# FPGA_LVDS.net
KiCad netlist of a schematic drawn in Altium Designer
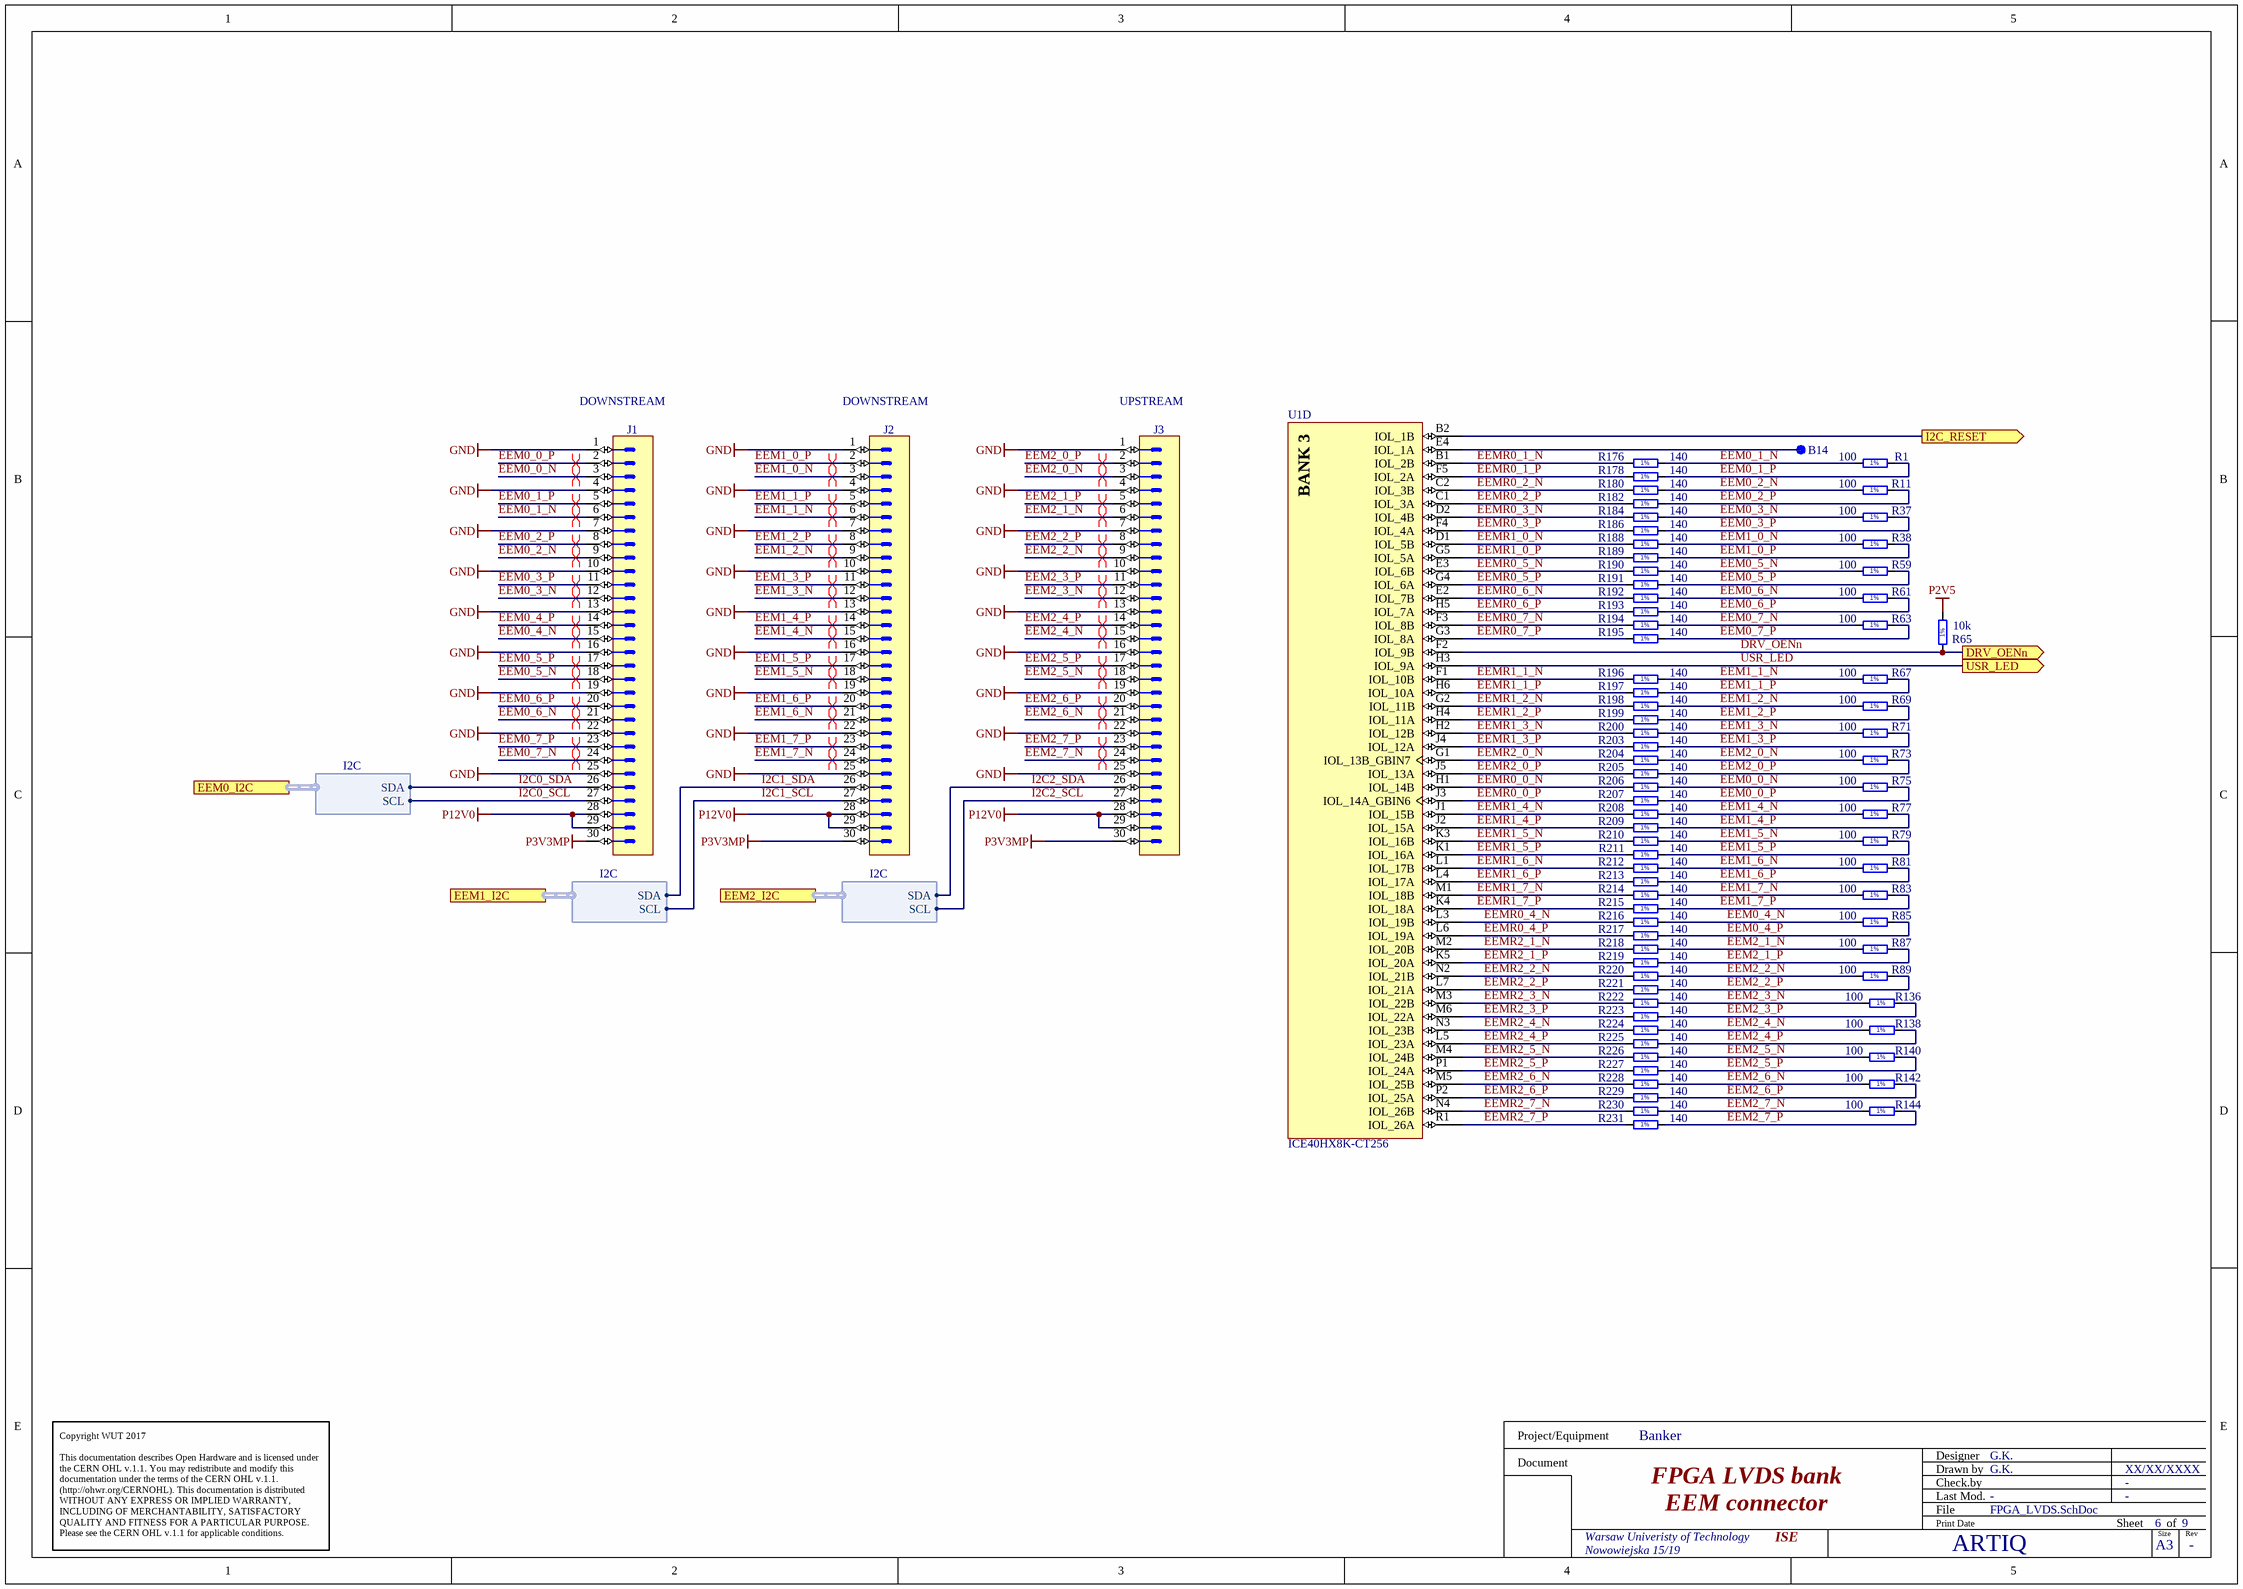
[diagram p0: FPGA_LVDS.SchDoc]

(export (version "E")
  (design (tool "Eeschema 10.0.6"))
  (components
    (comp (ref "B14")
      (value "SMD Pad")
      (footprint "C100")
      (description "Through Hole Pad")
      (fields (field (name "PART NUMBER") "SMD_PAD_D1MM") (field (name "AUTHOR") "CERN DEM JLC"))
      (libsource (lib "Eletro-mechanical") (part "Single SMD Pad (Round)"))
    )
    (comp (ref "J1")
      (value "~")
      (footprint "3M_N2530-6002RB")
      (description "Connector 30 Male")
      (fields
        (field (name "PART NUMBER") "3M_N2530-6002RB")
        (field (name "MANUFACTURER") "3M")
        (field (name "AUTHOR") "CERN DEM JLC")
      )
      (libsource (lib "Connectors") (part "Connector 30 Male"))
    )
    (comp (ref "J2")
      (value "~")
      (footprint "3M_N2530-6002RB")
      (description "Connector 30 Male")
      (fields
        (field (name "PART NUMBER") "3M_N2530-6002RB")
        (field (name "MANUFACTURER") "3M")
        (field (name "AUTHOR") "CERN DEM JLC")
      )
      (libsource (lib "Connectors") (part "Connector 30 Male"))
    )
    (comp (ref "J3")
      (value "~")
      (footprint "3M_N2530-6002RB")
      (description "Connector 30 Male")
      (fields
        (field (name "PART NUMBER") "3M_N2530-6002RB")
        (field (name "MANUFACTURER") "3M")
        (field (name "AUTHOR") "CERN DEM JLC")
      )
      (libsource (lib "Connectors") (part "Connector 30 Male"))
    )
    (comp (ref "R1")
      (value "100")
      (footprint "RESC1005X40N")
      (description "Resistor - 1%")
      (fields
        (field (name "PART NUMBER") "R0402_100R_1%_0.0625W_100PPM")
        (field (name "POWER") "0.0625W")
        (field (name "AUTHOR") "CERN DEM JLC")
      )
      (libsource (lib "Resistors") (part "Resistor - 1%"))
    )
    (comp (ref "R11")
      (value "100")
      (footprint "RESC1005X40N")
      (description "Resistor - 1%")
      (fields
        (field (name "PART NUMBER") "R0402_100R_1%_0.0625W_100PPM")
        (field (name "POWER") "0.0625W")
        (field (name "AUTHOR") "CERN DEM JLC")
      )
      (libsource (lib "Resistors") (part "Resistor - 1%"))
    )
    (comp (ref "R37")
      (value "100")
      (footprint "RESC1005X40N")
      (description "Resistor - 1%")
      (fields
        (field (name "PART NUMBER") "R0402_100R_1%_0.0625W_100PPM")
        (field (name "POWER") "0.0625W")
        (field (name "AUTHOR") "CERN DEM JLC")
      )
      (libsource (lib "Resistors") (part "Resistor - 1%"))
    )
    (comp (ref "R38")
      (value "100")
      (footprint "RESC1005X40N")
      (description "Resistor - 1%")
      (fields
        (field (name "PART NUMBER") "R0402_100R_1%_0.0625W_100PPM")
        (field (name "POWER") "0.0625W")
        (field (name "AUTHOR") "CERN DEM JLC")
      )
      (libsource (lib "Resistors") (part "Resistor - 1%"))
    )
    (comp (ref "R59")
      (value "100")
      (footprint "RESC1005X40N")
      (description "Resistor - 1%")
      (fields
        (field (name "PART NUMBER") "R0402_100R_1%_0.0625W_100PPM")
        (field (name "POWER") "0.0625W")
        (field (name "AUTHOR") "CERN DEM JLC")
      )
      (libsource (lib "Resistors") (part "Resistor - 1%"))
    )
    (comp (ref "R61")
      (value "100")
      (footprint "RESC1005X40N")
      (description "Resistor - 1%")
      (fields
        (field (name "PART NUMBER") "R0402_100R_1%_0.0625W_100PPM")
        (field (name "POWER") "0.0625W")
        (field (name "AUTHOR") "CERN DEM JLC")
      )
      (libsource (lib "Resistors") (part "Resistor - 1%"))
    )
    (comp (ref "R63")
      (value "100")
      (footprint "RESC1005X40N")
      (description "Resistor - 1%")
      (fields
        (field (name "PART NUMBER") "R0402_100R_1%_0.0625W_100PPM")
        (field (name "POWER") "0.0625W")
        (field (name "AUTHOR") "CERN DEM JLC")
      )
      (libsource (lib "Resistors") (part "Resistor - 1%"))
    )
    (comp (ref "R65")
      (value "10k")
      (footprint "RESC1005X40N")
      (description "Resistor - 1%")
      (fields
        (field (name "PART NUMBER") "R0402_10K_1%_0.0625W_100PPM")
        (field (name "POWER") "0.0625W")
        (field (name "AUTHOR") "CERN DEM JLC")
      )
      (libsource (lib "Resistors") (part "Resistor - 1%"))
    )
    (comp (ref "R67")
      (value "100")
      (footprint "RESC1005X40N")
      (description "Resistor - 1%")
      (fields
        (field (name "PART NUMBER") "R0402_100R_1%_0.0625W_100PPM")
        (field (name "POWER") "0.0625W")
        (field (name "AUTHOR") "CERN DEM JLC")
      )
      (libsource (lib "Resistors") (part "Resistor - 1%"))
    )
    (comp (ref "R69")
      (value "100")
      (footprint "RESC1005X40N")
      (description "Resistor - 1%")
      (fields
        (field (name "PART NUMBER") "R0402_100R_1%_0.0625W_100PPM")
        (field (name "POWER") "0.0625W")
        (field (name "AUTHOR") "CERN DEM JLC")
      )
      (libsource (lib "Resistors") (part "Resistor - 1%"))
    )
    (comp (ref "R71")
      (value "100")
      (footprint "RESC1005X40N")
      (description "Resistor - 1%")
      (fields
        (field (name "PART NUMBER") "R0402_100R_1%_0.0625W_100PPM")
        (field (name "POWER") "0.0625W")
        (field (name "AUTHOR") "CERN DEM JLC")
      )
      (libsource (lib "Resistors") (part "Resistor - 1%"))
    )
    (comp (ref "R73")
      (value "100")
      (footprint "RESC1005X40N")
      (description "Resistor - 1%")
      (fields
        (field (name "PART NUMBER") "R0402_100R_1%_0.0625W_100PPM")
        (field (name "POWER") "0.0625W")
        (field (name "AUTHOR") "CERN DEM JLC")
      )
      (libsource (lib "Resistors") (part "Resistor - 1%"))
    )
    (comp (ref "R75")
      (value "100")
      (footprint "RESC1005X40N")
      (description "Resistor - 1%")
      (fields
        (field (name "PART NUMBER") "R0402_100R_1%_0.0625W_100PPM")
        (field (name "POWER") "0.0625W")
        (field (name "AUTHOR") "CERN DEM JLC")
      )
      (libsource (lib "Resistors") (part "Resistor - 1%"))
    )
    (comp (ref "R77")
      (value "100")
      (footprint "RESC1005X40N")
      (description "Resistor - 1%")
      (fields
        (field (name "PART NUMBER") "R0402_100R_1%_0.0625W_100PPM")
        (field (name "POWER") "0.0625W")
        (field (name "AUTHOR") "CERN DEM JLC")
      )
      (libsource (lib "Resistors") (part "Resistor - 1%"))
    )
    (comp (ref "R79")
      (value "100")
      (footprint "RESC1005X40N")
      (description "Resistor - 1%")
      (fields
        (field (name "PART NUMBER") "R0402_100R_1%_0.0625W_100PPM")
        (field (name "POWER") "0.0625W")
        (field (name "AUTHOR") "CERN DEM JLC")
      )
      (libsource (lib "Resistors") (part "Resistor - 1%"))
    )
    (comp (ref "R81")
      (value "100")
      (footprint "RESC1005X40N")
      (description "Resistor - 1%")
      (fields
        (field (name "PART NUMBER") "R0402_100R_1%_0.0625W_100PPM")
        (field (name "POWER") "0.0625W")
        (field (name "AUTHOR") "CERN DEM JLC")
      )
      (libsource (lib "Resistors") (part "Resistor - 1%"))
    )
    (comp (ref "R83")
      (value "100")
      (footprint "RESC1005X40N")
      (description "Resistor - 1%")
      (fields
        (field (name "PART NUMBER") "R0402_100R_1%_0.0625W_100PPM")
        (field (name "POWER") "0.0625W")
        (field (name "AUTHOR") "CERN DEM JLC")
      )
      (libsource (lib "Resistors") (part "Resistor - 1%"))
    )
    (comp (ref "R85")
      (value "100")
      (footprint "RESC1005X40N")
      (description "Resistor - 1%")
      (fields
        (field (name "PART NUMBER") "R0402_100R_1%_0.0625W_100PPM")
        (field (name "POWER") "0.0625W")
        (field (name "AUTHOR") "CERN DEM JLC")
      )
      (libsource (lib "Resistors") (part "Resistor - 1%"))
    )
    (comp (ref "R87")
      (value "100")
      (footprint "RESC1005X40N")
      (description "Resistor - 1%")
      (fields
        (field (name "PART NUMBER") "R0402_100R_1%_0.0625W_100PPM")
        (field (name "POWER") "0.0625W")
        (field (name "AUTHOR") "CERN DEM JLC")
      )
      (libsource (lib "Resistors") (part "Resistor - 1%"))
    )
    (comp (ref "R89")
      (value "100")
      (footprint "RESC1005X40N")
      (description "Resistor - 1%")
      (fields
        (field (name "PART NUMBER") "R0402_100R_1%_0.0625W_100PPM")
        (field (name "POWER") "0.0625W")
        (field (name "AUTHOR") "CERN DEM JLC")
      )
      (libsource (lib "Resistors") (part "Resistor - 1%"))
    )
    (comp (ref "R136")
      (value "100")
      (footprint "RESC1005X40N")
      (description "Resistor - 1%")
      (fields
        (field (name "PART NUMBER") "R0402_100R_1%_0.0625W_100PPM")
        (field (name "POWER") "0.0625W")
        (field (name "AUTHOR") "CERN DEM JLC")
      )
      (libsource (lib "Resistors") (part "Resistor - 1%"))
    )
    (comp (ref "R138")
      (value "100")
      (footprint "RESC1005X40N")
      (description "Resistor - 1%")
      (fields
        (field (name "PART NUMBER") "R0402_100R_1%_0.0625W_100PPM")
        (field (name "POWER") "0.0625W")
        (field (name "AUTHOR") "CERN DEM JLC")
      )
      (libsource (lib "Resistors") (part "Resistor - 1%"))
    )
    (comp (ref "R140")
      (value "100")
      (footprint "RESC1005X40N")
      (description "Resistor - 1%")
      (fields
        (field (name "PART NUMBER") "R0402_100R_1%_0.0625W_100PPM")
        (field (name "POWER") "0.0625W")
        (field (name "AUTHOR") "CERN DEM JLC")
      )
      (libsource (lib "Resistors") (part "Resistor - 1%"))
    )
    (comp (ref "R142")
      (value "100")
      (footprint "RESC1005X40N")
      (description "Resistor - 1%")
      (fields
        (field (name "PART NUMBER") "R0402_100R_1%_0.0625W_100PPM")
        (field (name "POWER") "0.0625W")
        (field (name "AUTHOR") "CERN DEM JLC")
      )
      (libsource (lib "Resistors") (part "Resistor - 1%"))
    )
    (comp (ref "R144")
      (value "100")
      (footprint "RESC1005X40N")
      (description "Resistor - 1%")
      (fields
        (field (name "PART NUMBER") "R0402_100R_1%_0.0625W_100PPM")
        (field (name "POWER") "0.0625W")
        (field (name "AUTHOR") "CERN DEM JLC")
      )
      (libsource (lib "Resistors") (part "Resistor - 1%"))
    )
    (comp (ref "R176")
      (value "140")
      (footprint "RESC0603X28N")
      (description "Resistor - 1%")
      (fields
        (field (name "PART NUMBER") "R0201_140R_1%_0.05W_200PPM")
        (field (name "POWER") "0.05W")
        (field (name "AUTHOR") "CERN DEM MR")
      )
      (libsource (lib "Resistors") (part "Resistor - 1%"))
    )
    (comp (ref "R178")
      (value "140")
      (footprint "RESC0603X28N")
      (description "Resistor - 1%")
      (fields
        (field (name "PART NUMBER") "R0201_140R_1%_0.05W_200PPM")
        (field (name "POWER") "0.05W")
        (field (name "AUTHOR") "CERN DEM MR")
      )
      (libsource (lib "Resistors") (part "Resistor - 1%"))
    )
    (comp (ref "R180")
      (value "140")
      (footprint "RESC0603X28N")
      (description "Resistor - 1%")
      (fields
        (field (name "PART NUMBER") "R0201_140R_1%_0.05W_200PPM")
        (field (name "POWER") "0.05W")
        (field (name "AUTHOR") "CERN DEM MR")
      )
      (libsource (lib "Resistors") (part "Resistor - 1%"))
    )
    (comp (ref "R182")
      (value "140")
      (footprint "RESC0603X28N")
      (description "Resistor - 1%")
      (fields
        (field (name "PART NUMBER") "R0201_140R_1%_0.05W_200PPM")
        (field (name "POWER") "0.05W")
        (field (name "AUTHOR") "CERN DEM MR")
      )
      (libsource (lib "Resistors") (part "Resistor - 1%"))
    )
    (comp (ref "R184")
      (value "140")
      (footprint "RESC0603X28N")
      (description "Resistor - 1%")
      (fields
        (field (name "PART NUMBER") "R0201_140R_1%_0.05W_200PPM")
        (field (name "POWER") "0.05W")
        (field (name "AUTHOR") "CERN DEM MR")
      )
      (libsource (lib "Resistors") (part "Resistor - 1%"))
    )
    (comp (ref "R186")
      (value "140")
      (footprint "RESC0603X28N")
      (description "Resistor - 1%")
      (fields
        (field (name "PART NUMBER") "R0201_140R_1%_0.05W_200PPM")
        (field (name "POWER") "0.05W")
        (field (name "AUTHOR") "CERN DEM MR")
      )
      (libsource (lib "Resistors") (part "Resistor - 1%"))
    )
    (comp (ref "R188")
      (value "140")
      (footprint "RESC0603X28N")
      (description "Resistor - 1%")
      (fields
        (field (name "PART NUMBER") "R0201_140R_1%_0.05W_200PPM")
        (field (name "POWER") "0.05W")
        (field (name "AUTHOR") "CERN DEM MR")
      )
      (libsource (lib "Resistors") (part "Resistor - 1%"))
    )
    (comp (ref "R189")
      (value "140")
      (footprint "RESC0603X28N")
      (description "Resistor - 1%")
      (fields
        (field (name "PART NUMBER") "R0201_140R_1%_0.05W_200PPM")
        (field (name "POWER") "0.05W")
        (field (name "AUTHOR") "CERN DEM MR")
      )
      (libsource (lib "Resistors") (part "Resistor - 1%"))
    )
    (comp (ref "R190")
      (value "140")
      (footprint "RESC0603X28N")
      (description "Resistor - 1%")
      (fields
        (field (name "PART NUMBER") "R0201_140R_1%_0.05W_200PPM")
        (field (name "POWER") "0.05W")
        (field (name "AUTHOR") "CERN DEM MR")
      )
      (libsource (lib "Resistors") (part "Resistor - 1%"))
    )
    (comp (ref "R191")
      (value "140")
      (footprint "RESC0603X28N")
      (description "Resistor - 1%")
      (fields
        (field (name "PART NUMBER") "R0201_140R_1%_0.05W_200PPM")
        (field (name "POWER") "0.05W")
        (field (name "AUTHOR") "CERN DEM MR")
      )
      (libsource (lib "Resistors") (part "Resistor - 1%"))
    )
    (comp (ref "R192")
      (value "140")
      (footprint "RESC0603X28N")
      (description "Resistor - 1%")
      (fields
        (field (name "PART NUMBER") "R0201_140R_1%_0.05W_200PPM")
        (field (name "POWER") "0.05W")
        (field (name "AUTHOR") "CERN DEM MR")
      )
      (libsource (lib "Resistors") (part "Resistor - 1%"))
    )
    (comp (ref "R193")
      (value "140")
      (footprint "RESC0603X28N")
      (description "Resistor - 1%")
      (fields
        (field (name "PART NUMBER") "R0201_140R_1%_0.05W_200PPM")
        (field (name "POWER") "0.05W")
        (field (name "AUTHOR") "CERN DEM MR")
      )
      (libsource (lib "Resistors") (part "Resistor - 1%"))
    )
    (comp (ref "R194")
      (value "140")
      (footprint "RESC0603X28N")
      (description "Resistor - 1%")
      (fields
        (field (name "PART NUMBER") "R0201_140R_1%_0.05W_200PPM")
        (field (name "POWER") "0.05W")
        (field (name "AUTHOR") "CERN DEM MR")
      )
      (libsource (lib "Resistors") (part "Resistor - 1%"))
    )
    (comp (ref "R195")
      (value "140")
      (footprint "RESC0603X28N")
      (description "Resistor - 1%")
      (fields
        (field (name "PART NUMBER") "R0201_140R_1%_0.05W_200PPM")
        (field (name "POWER") "0.05W")
        (field (name "AUTHOR") "CERN DEM MR")
      )
      (libsource (lib "Resistors") (part "Resistor - 1%"))
    )
    (comp (ref "R196")
      (value "140")
      (footprint "RESC0603X28N")
      (description "Resistor - 1%")
      (fields
        (field (name "PART NUMBER") "R0201_140R_1%_0.05W_200PPM")
        (field (name "POWER") "0.05W")
        (field (name "AUTHOR") "CERN DEM MR")
      )
      (libsource (lib "Resistors") (part "Resistor - 1%"))
    )
    (comp (ref "R197")
      (value "140")
      (footprint "RESC0603X28N")
      (description "Resistor - 1%")
      (fields
        (field (name "PART NUMBER") "R0201_140R_1%_0.05W_200PPM")
        (field (name "POWER") "0.05W")
        (field (name "AUTHOR") "CERN DEM MR")
      )
      (libsource (lib "Resistors") (part "Resistor - 1%"))
    )
    (comp (ref "R198")
      (value "140")
      (footprint "RESC0603X28N")
      (description "Resistor - 1%")
      (fields
        (field (name "PART NUMBER") "R0201_140R_1%_0.05W_200PPM")
        (field (name "POWER") "0.05W")
        (field (name "AUTHOR") "CERN DEM MR")
      )
      (libsource (lib "Resistors") (part "Resistor - 1%"))
    )
    (comp (ref "R199")
      (value "140")
      (footprint "RESC0603X28N")
      (description "Resistor - 1%")
      (fields
        (field (name "PART NUMBER") "R0201_140R_1%_0.05W_200PPM")
        (field (name "POWER") "0.05W")
        (field (name "AUTHOR") "CERN DEM MR")
      )
      (libsource (lib "Resistors") (part "Resistor - 1%"))
    )
    (comp (ref "R200")
      (value "140")
      (footprint "RESC0603X28N")
      (description "Resistor - 1%")
      (fields
        (field (name "PART NUMBER") "R0201_140R_1%_0.05W_200PPM")
        (field (name "POWER") "0.05W")
        (field (name "AUTHOR") "CERN DEM MR")
      )
      (libsource (lib "Resistors") (part "Resistor - 1%"))
    )
    (comp (ref "R203")
      (value "140")
      (footprint "RESC0603X28N")
      (description "Resistor - 1%")
      (fields
        (field (name "PART NUMBER") "R0201_140R_1%_0.05W_200PPM")
        (field (name "POWER") "0.05W")
        (field (name "AUTHOR") "CERN DEM MR")
      )
      (libsource (lib "Resistors") (part "Resistor - 1%"))
    )
    (comp (ref "R204")
      (value "140")
      (footprint "RESC0603X28N")
      (description "Resistor - 1%")
      (fields
        (field (name "PART NUMBER") "R0201_140R_1%_0.05W_200PPM")
        (field (name "POWER") "0.05W")
        (field (name "AUTHOR") "CERN DEM MR")
      )
      (libsource (lib "Resistors") (part "Resistor - 1%"))
    )
    (comp (ref "R205")
      (value "140")
      (footprint "RESC0603X28N")
      (description "Resistor - 1%")
      (fields
        (field (name "PART NUMBER") "R0201_140R_1%_0.05W_200PPM")
        (field (name "POWER") "0.05W")
        (field (name "AUTHOR") "CERN DEM MR")
      )
      (libsource (lib "Resistors") (part "Resistor - 1%"))
    )
    (comp (ref "R206")
      (value "140")
      (footprint "RESC0603X28N")
      (description "Resistor - 1%")
      (fields
        (field (name "PART NUMBER") "R0201_140R_1%_0.05W_200PPM")
        (field (name "POWER") "0.05W")
        (field (name "AUTHOR") "CERN DEM MR")
      )
      (libsource (lib "Resistors") (part "Resistor - 1%"))
    )
    (comp (ref "R207")
      (value "140")
      (footprint "RESC0603X28N")
      (description "Resistor - 1%")
      (fields
        (field (name "PART NUMBER") "R0201_140R_1%_0.05W_200PPM")
        (field (name "POWER") "0.05W")
        (field (name "AUTHOR") "CERN DEM MR")
      )
      (libsource (lib "Resistors") (part "Resistor - 1%"))
    )
    (comp (ref "R208")
      (value "140")
      (footprint "RESC0603X28N")
      (description "Resistor - 1%")
      (fields
        (field (name "PART NUMBER") "R0201_140R_1%_0.05W_200PPM")
        (field (name "POWER") "0.05W")
        (field (name "AUTHOR") "CERN DEM MR")
      )
      (libsource (lib "Resistors") (part "Resistor - 1%"))
    )
    (comp (ref "R209")
      (value "140")
      (footprint "RESC0603X28N")
      (description "Resistor - 1%")
      (fields
        (field (name "PART NUMBER") "R0201_140R_1%_0.05W_200PPM")
        (field (name "POWER") "0.05W")
        (field (name "AUTHOR") "CERN DEM MR")
      )
      (libsource (lib "Resistors") (part "Resistor - 1%"))
    )
    (comp (ref "R210")
      (value "140")
      (footprint "RESC0603X28N")
      (description "Resistor - 1%")
      (fields
        (field (name "PART NUMBER") "R0201_140R_1%_0.05W_200PPM")
        (field (name "POWER") "0.05W")
        (field (name "AUTHOR") "CERN DEM MR")
      )
      (libsource (lib "Resistors") (part "Resistor - 1%"))
    )
    (comp (ref "R211")
      (value "140")
      (footprint "RESC0603X28N")
      (description "Resistor - 1%")
      (fields
        (field (name "PART NUMBER") "R0201_140R_1%_0.05W_200PPM")
        (field (name "POWER") "0.05W")
        (field (name "AUTHOR") "CERN DEM MR")
      )
      (libsource (lib "Resistors") (part "Resistor - 1%"))
    )
    (comp (ref "R212")
      (value "140")
      (footprint "RESC0603X28N")
      (description "Resistor - 1%")
      (fields
        (field (name "PART NUMBER") "R0201_140R_1%_0.05W_200PPM")
        (field (name "POWER") "0.05W")
        (field (name "AUTHOR") "CERN DEM MR")
      )
      (libsource (lib "Resistors") (part "Resistor - 1%"))
    )
    (comp (ref "R213")
      (value "140")
      (footprint "RESC0603X28N")
      (description "Resistor - 1%")
      (fields
        (field (name "PART NUMBER") "R0201_140R_1%_0.05W_200PPM")
        (field (name "POWER") "0.05W")
        (field (name "AUTHOR") "CERN DEM MR")
      )
      (libsource (lib "Resistors") (part "Resistor - 1%"))
    )
    (comp (ref "R214")
      (value "140")
      (footprint "RESC0603X28N")
      (description "Resistor - 1%")
      (fields
        (field (name "PART NUMBER") "R0201_140R_1%_0.05W_200PPM")
        (field (name "POWER") "0.05W")
        (field (name "AUTHOR") "CERN DEM MR")
      )
      (libsource (lib "Resistors") (part "Resistor - 1%"))
    )
    (comp (ref "R215")
      (value "140")
      (footprint "RESC0603X28N")
      (description "Resistor - 1%")
      (fields
        (field (name "PART NUMBER") "R0201_140R_1%_0.05W_200PPM")
        (field (name "POWER") "0.05W")
        (field (name "AUTHOR") "CERN DEM MR")
      )
      (libsource (lib "Resistors") (part "Resistor - 1%"))
    )
    (comp (ref "R216")
      (value "140")
      (footprint "RESC0603X28N")
      (description "Resistor - 1%")
      (fields
        (field (name "PART NUMBER") "R0201_140R_1%_0.05W_200PPM")
        (field (name "POWER") "0.05W")
        (field (name "AUTHOR") "CERN DEM MR")
      )
      (libsource (lib "Resistors") (part "Resistor - 1%"))
    )
    (comp (ref "R217")
      (value "140")
      (footprint "RESC0603X28N")
      (description "Resistor - 1%")
      (fields
        (field (name "PART NUMBER") "R0201_140R_1%_0.05W_200PPM")
        (field (name "POWER") "0.05W")
        (field (name "AUTHOR") "CERN DEM MR")
      )
      (libsource (lib "Resistors") (part "Resistor - 1%"))
    )
    (comp (ref "R218")
      (value "140")
      (footprint "RESC0603X28N")
      (description "Resistor - 1%")
      (fields
        (field (name "PART NUMBER") "R0201_140R_1%_0.05W_200PPM")
        (field (name "POWER") "0.05W")
        (field (name "AUTHOR") "CERN DEM MR")
      )
      (libsource (lib "Resistors") (part "Resistor - 1%"))
    )
    (comp (ref "R219")
      (value "140")
      (footprint "RESC0603X28N")
      (description "Resistor - 1%")
      (fields
        (field (name "PART NUMBER") "R0201_140R_1%_0.05W_200PPM")
        (field (name "POWER") "0.05W")
        (field (name "AUTHOR") "CERN DEM MR")
      )
      (libsource (lib "Resistors") (part "Resistor - 1%"))
    )
    (comp (ref "R220")
      (value "140")
      (footprint "RESC0603X28N")
      (description "Resistor - 1%")
      (fields
        (field (name "PART NUMBER") "R0201_140R_1%_0.05W_200PPM")
        (field (name "POWER") "0.05W")
        (field (name "AUTHOR") "CERN DEM MR")
      )
      (libsource (lib "Resistors") (part "Resistor - 1%"))
    )
    (comp (ref "R221")
      (value "140")
      (footprint "RESC0603X28N")
      (description "Resistor - 1%")
      (fields
        (field (name "PART NUMBER") "R0201_140R_1%_0.05W_200PPM")
        (field (name "POWER") "0.05W")
        (field (name "AUTHOR") "CERN DEM MR")
      )
      (libsource (lib "Resistors") (part "Resistor - 1%"))
    )
    (comp (ref "R222")
      (value "140")
      (footprint "RESC0603X28N")
      (description "Resistor - 1%")
      (fields
        (field (name "PART NUMBER") "R0201_140R_1%_0.05W_200PPM")
        (field (name "POWER") "0.05W")
        (field (name "AUTHOR") "CERN DEM MR")
      )
      (libsource (lib "Resistors") (part "Resistor - 1%"))
    )
    (comp (ref "R223")
      (value "140")
      (footprint "RESC0603X28N")
      (description "Resistor - 1%")
      (fields
        (field (name "PART NUMBER") "R0201_140R_1%_0.05W_200PPM")
        (field (name "POWER") "0.05W")
        (field (name "AUTHOR") "CERN DEM MR")
      )
      (libsource (lib "Resistors") (part "Resistor - 1%"))
    )
    (comp (ref "R224")
      (value "140")
      (footprint "RESC0603X28N")
      (description "Resistor - 1%")
      (fields
        (field (name "PART NUMBER") "R0201_140R_1%_0.05W_200PPM")
        (field (name "POWER") "0.05W")
        (field (name "AUTHOR") "CERN DEM MR")
      )
      (libsource (lib "Resistors") (part "Resistor - 1%"))
    )
    (comp (ref "R225")
      (value "140")
      (footprint "RESC0603X28N")
      (description "Resistor - 1%")
      (fields
        (field (name "PART NUMBER") "R0201_140R_1%_0.05W_200PPM")
        (field (name "POWER") "0.05W")
        (field (name "AUTHOR") "CERN DEM MR")
      )
      (libsource (lib "Resistors") (part "Resistor - 1%"))
    )
    (comp (ref "R226")
      (value "140")
      (footprint "RESC0603X28N")
      (description "Resistor - 1%")
      (fields
        (field (name "PART NUMBER") "R0201_140R_1%_0.05W_200PPM")
        (field (name "POWER") "0.05W")
        (field (name "AUTHOR") "CERN DEM MR")
      )
      (libsource (lib "Resistors") (part "Resistor - 1%"))
    )
    (comp (ref "R227")
      (value "140")
      (footprint "RESC0603X28N")
      (description "Resistor - 1%")
      (fields
        (field (name "PART NUMBER") "R0201_140R_1%_0.05W_200PPM")
        (field (name "POWER") "0.05W")
        (field (name "AUTHOR") "CERN DEM MR")
      )
      (libsource (lib "Resistors") (part "Resistor - 1%"))
    )
    (comp (ref "R228")
      (value "140")
      (footprint "RESC0603X28N")
      (description "Resistor - 1%")
      (fields
        (field (name "PART NUMBER") "R0201_140R_1%_0.05W_200PPM")
        (field (name "POWER") "0.05W")
        (field (name "AUTHOR") "CERN DEM MR")
      )
      (libsource (lib "Resistors") (part "Resistor - 1%"))
    )
    (comp (ref "R229")
      (value "140")
      (footprint "RESC0603X28N")
      (description "Resistor - 1%")
      (fields
        (field (name "PART NUMBER") "R0201_140R_1%_0.05W_200PPM")
        (field (name "POWER") "0.05W")
        (field (name "AUTHOR") "CERN DEM MR")
      )
      (libsource (lib "Resistors") (part "Resistor - 1%"))
    )
    (comp (ref "R230")
      (value "140")
      (footprint "RESC0603X28N")
      (description "Resistor - 1%")
      (fields
        (field (name "PART NUMBER") "R0201_140R_1%_0.05W_200PPM")
        (field (name "POWER") "0.05W")
        (field (name "AUTHOR") "CERN DEM MR")
      )
      (libsource (lib "Resistors") (part "Resistor - 1%"))
    )
    (comp (ref "R231")
      (value "140")
      (footprint "RESC0603X28N")
      (description "Resistor - 1%")
      (fields
        (field (name "PART NUMBER") "R0201_140R_1%_0.05W_200PPM")
        (field (name "POWER") "0.05W")
        (field (name "AUTHOR") "CERN DEM MR")
      )
      (libsource (lib "Resistors") (part "Resistor - 1%"))
    )
    (comp (ref "U1")
      (value "ICE40HX8K-CT256")
      (footprint "LATC-caBGA-256")
      (fields (field (name "MANUFACTURER") "Lattice Semiconductor"))
      (libsource (lib "Altium Content Vault") (part "LATC-HX8K-caBGA-256"))
    )
  )
  (nets
    (net (code "2") (name "/DRV_OENn") (class "Default")
      (node (ref "R65") (pin "1") (pinfunction "1_1") (pintype "passive"))
      (node (ref "U1") (pin "F2") (pinfunction "IOL_9B_F2") (pintype "bidirectional"))
    )
    (net (code "3") (name "/EEM0_0_N") (class "Default")
      (node (ref "J1") (pin "3") (pinfunction "3_3") (pintype "bidirectional"))
      (node (ref "R206") (pin "2") (pinfunction "2_2") (pintype "passive"))
      (node (ref "R75") (pin "1") (pinfunction "1_1") (pintype "passive"))
    )
    (net (code "4") (name "/EEM0_0_P") (class "Default")
      (node (ref "J1") (pin "2") (pinfunction "2_2") (pintype "bidirectional"))
      (node (ref "R207") (pin "2") (pinfunction "2_2") (pintype "passive"))
      (node (ref "R75") (pin "2") (pinfunction "2_2") (pintype "passive"))
    )
    (net (code "5") (name "/EEM0_1_N") (class "Default")
      (node (ref "J1") (pin "6") (pinfunction "6_6") (pintype "bidirectional"))
      (node (ref "R1") (pin "1") (pinfunction "1_1") (pintype "passive"))
      (node (ref "R176") (pin "2") (pinfunction "2_2") (pintype "passive"))
    )
    (net (code "6") (name "/EEM0_1_P") (class "Default")
      (node (ref "J1") (pin "5") (pinfunction "5_5") (pintype "bidirectional"))
      (node (ref "R1") (pin "2") (pinfunction "2_2") (pintype "passive"))
      (node (ref "R178") (pin "2") (pinfunction "2_2") (pintype "passive"))
    )
    (net (code "7") (name "/EEM0_2_N") (class "Default")
      (node (ref "J1") (pin "9") (pinfunction "9_9") (pintype "bidirectional"))
      (node (ref "R11") (pin "1") (pinfunction "1_1") (pintype "passive"))
      (node (ref "R180") (pin "2") (pinfunction "2_2") (pintype "passive"))
    )
    (net (code "8") (name "/EEM0_2_P") (class "Default")
      (node (ref "J1") (pin "8") (pinfunction "8_8") (pintype "bidirectional"))
      (node (ref "R11") (pin "2") (pinfunction "2_2") (pintype "passive"))
      (node (ref "R182") (pin "2") (pinfunction "2_2") (pintype "passive"))
    )
    (net (code "9") (name "/EEM0_3_N") (class "Default")
      (node (ref "J1") (pin "12") (pinfunction "12_12") (pintype "bidirectional"))
      (node (ref "R184") (pin "2") (pinfunction "2_2") (pintype "passive"))
      (node (ref "R37") (pin "1") (pinfunction "1_1") (pintype "passive"))
    )
    (net (code "10") (name "/EEM0_3_P") (class "Default")
      (node (ref "J1") (pin "11") (pinfunction "11_11") (pintype "bidirectional"))
      (node (ref "R186") (pin "2") (pinfunction "2_2") (pintype "passive"))
      (node (ref "R37") (pin "2") (pinfunction "2_2") (pintype "passive"))
    )
    (net (code "11") (name "/EEM0_4_N") (class "Default")
      (node (ref "J1") (pin "15") (pinfunction "15_15") (pintype "bidirectional"))
      (node (ref "R216") (pin "2") (pinfunction "2_2") (pintype "passive"))
      (node (ref "R85") (pin "1") (pinfunction "1_1") (pintype "passive"))
    )
    (net (code "12") (name "/EEM0_4_P") (class "Default")
      (node (ref "J1") (pin "14") (pinfunction "14_14") (pintype "bidirectional"))
      (node (ref "R217") (pin "2") (pinfunction "2_2") (pintype "passive"))
      (node (ref "R85") (pin "2") (pinfunction "2_2") (pintype "passive"))
    )
    (net (code "13") (name "/EEM0_5_N") (class "Default")
      (node (ref "J1") (pin "18") (pinfunction "18_18") (pintype "bidirectional"))
      (node (ref "R190") (pin "2") (pinfunction "2_2") (pintype "passive"))
      (node (ref "R59") (pin "1") (pinfunction "1_1") (pintype "passive"))
    )
    (net (code "14") (name "/EEM0_5_P") (class "Default")
      (node (ref "J1") (pin "17") (pinfunction "17_17") (pintype "bidirectional"))
      (node (ref "R191") (pin "2") (pinfunction "2_2") (pintype "passive"))
      (node (ref "R59") (pin "2") (pinfunction "2_2") (pintype "passive"))
    )
    (net (code "15") (name "/EEM0_6_N") (class "Default")
      (node (ref "J1") (pin "21") (pinfunction "21_21") (pintype "bidirectional"))
      (node (ref "R192") (pin "2") (pinfunction "2_2") (pintype "passive"))
      (node (ref "R61") (pin "1") (pinfunction "1_1") (pintype "passive"))
    )
    (net (code "16") (name "/EEM0_6_P") (class "Default")
      (node (ref "J1") (pin "20") (pinfunction "20_20") (pintype "bidirectional"))
      (node (ref "R193") (pin "2") (pinfunction "2_2") (pintype "passive"))
      (node (ref "R61") (pin "2") (pinfunction "2_2") (pintype "passive"))
    )
    (net (code "17") (name "/EEM0_7_N") (class "Default")
      (node (ref "J1") (pin "24") (pinfunction "24_24") (pintype "bidirectional"))
      (node (ref "R194") (pin "2") (pinfunction "2_2") (pintype "passive"))
      (node (ref "R63") (pin "1") (pinfunction "1_1") (pintype "passive"))
    )
    (net (code "18") (name "/EEM0_7_P") (class "Default")
      (node (ref "J1") (pin "23") (pinfunction "23_23") (pintype "bidirectional"))
      (node (ref "R195") (pin "2") (pinfunction "2_2") (pintype "passive"))
      (node (ref "R63") (pin "2") (pinfunction "2_2") (pintype "passive"))
    )
    (net (code "19") (name "/EEM1_0_N") (class "Default")
      (node (ref "J2") (pin "3") (pinfunction "3_3") (pintype "bidirectional"))
      (node (ref "R188") (pin "2") (pinfunction "2_2") (pintype "passive"))
      (node (ref "R38") (pin "1") (pinfunction "1_1") (pintype "passive"))
    )
    (net (code "20") (name "/EEM1_0_P") (class "Default")
      (node (ref "J2") (pin "2") (pinfunction "2_2") (pintype "bidirectional"))
      (node (ref "R189") (pin "2") (pinfunction "2_2") (pintype "passive"))
      (node (ref "R38") (pin "2") (pinfunction "2_2") (pintype "passive"))
    )
    (net (code "21") (name "/EEM1_1_N") (class "Default")
      (node (ref "J2") (pin "6") (pinfunction "6_6") (pintype "bidirectional"))
      (node (ref "R196") (pin "2") (pinfunction "2_2") (pintype "passive"))
      (node (ref "R67") (pin "1") (pinfunction "1_1") (pintype "passive"))
    )
    (net (code "22") (name "/EEM1_1_P") (class "Default")
      (node (ref "J2") (pin "5") (pinfunction "5_5") (pintype "bidirectional"))
      (node (ref "R197") (pin "2") (pinfunction "2_2") (pintype "passive"))
      (node (ref "R67") (pin "2") (pinfunction "2_2") (pintype "passive"))
    )
    (net (code "23") (name "/EEM1_2_N") (class "Default")
      (node (ref "J2") (pin "9") (pinfunction "9_9") (pintype "bidirectional"))
      (node (ref "R198") (pin "2") (pinfunction "2_2") (pintype "passive"))
      (node (ref "R69") (pin "1") (pinfunction "1_1") (pintype "passive"))
    )
    (net (code "24") (name "/EEM1_2_P") (class "Default")
      (node (ref "J2") (pin "8") (pinfunction "8_8") (pintype "bidirectional"))
      (node (ref "R199") (pin "2") (pinfunction "2_2") (pintype "passive"))
      (node (ref "R69") (pin "2") (pinfunction "2_2") (pintype "passive"))
    )
    (net (code "25") (name "/EEM1_3_N") (class "Default")
      (node (ref "J2") (pin "12") (pinfunction "12_12") (pintype "bidirectional"))
      (node (ref "R200") (pin "2") (pinfunction "2_2") (pintype "passive"))
      (node (ref "R71") (pin "1") (pinfunction "1_1") (pintype "passive"))
    )
    (net (code "26") (name "/EEM1_3_P") (class "Default")
      (node (ref "J2") (pin "11") (pinfunction "11_11") (pintype "bidirectional"))
      (node (ref "R203") (pin "2") (pinfunction "2_2") (pintype "passive"))
      (node (ref "R71") (pin "2") (pinfunction "2_2") (pintype "passive"))
    )
    (net (code "27") (name "/EEM1_4_N") (class "Default")
      (node (ref "J2") (pin "15") (pinfunction "15_15") (pintype "bidirectional"))
      (node (ref "R208") (pin "2") (pinfunction "2_2") (pintype "passive"))
      (node (ref "R77") (pin "1") (pinfunction "1_1") (pintype "passive"))
    )
    (net (code "28") (name "/EEM1_4_P") (class "Default")
      (node (ref "J2") (pin "14") (pinfunction "14_14") (pintype "bidirectional"))
      (node (ref "R209") (pin "2") (pinfunction "2_2") (pintype "passive"))
      (node (ref "R77") (pin "2") (pinfunction "2_2") (pintype "passive"))
    )
    (net (code "29") (name "/EEM1_5_N") (class "Default")
      (node (ref "J2") (pin "18") (pinfunction "18_18") (pintype "bidirectional"))
      (node (ref "R210") (pin "2") (pinfunction "2_2") (pintype "passive"))
      (node (ref "R79") (pin "1") (pinfunction "1_1") (pintype "passive"))
    )
    (net (code "30") (name "/EEM1_5_P") (class "Default")
      (node (ref "J2") (pin "17") (pinfunction "17_17") (pintype "bidirectional"))
      (node (ref "R211") (pin "2") (pinfunction "2_2") (pintype "passive"))
      (node (ref "R79") (pin "2") (pinfunction "2_2") (pintype "passive"))
    )
    (net (code "31") (name "/EEM1_6_N") (class "Default")
      (node (ref "J2") (pin "21") (pinfunction "21_21") (pintype "bidirectional"))
      (node (ref "R212") (pin "2") (pinfunction "2_2") (pintype "passive"))
      (node (ref "R81") (pin "1") (pinfunction "1_1") (pintype "passive"))
    )
    (net (code "32") (name "/EEM1_6_P") (class "Default")
      (node (ref "J2") (pin "20") (pinfunction "20_20") (pintype "bidirectional"))
      (node (ref "R213") (pin "2") (pinfunction "2_2") (pintype "passive"))
      (node (ref "R81") (pin "2") (pinfunction "2_2") (pintype "passive"))
    )
    (net (code "33") (name "/EEM1_7_N") (class "Default")
      (node (ref "J2") (pin "24") (pinfunction "24_24") (pintype "bidirectional"))
      (node (ref "R214") (pin "2") (pinfunction "2_2") (pintype "passive"))
      (node (ref "R83") (pin "1") (pinfunction "1_1") (pintype "passive"))
    )
    (net (code "34") (name "/EEM1_7_P") (class "Default")
      (node (ref "J2") (pin "23") (pinfunction "23_23") (pintype "bidirectional"))
      (node (ref "R215") (pin "2") (pinfunction "2_2") (pintype "passive"))
      (node (ref "R83") (pin "2") (pinfunction "2_2") (pintype "passive"))
    )
    (net (code "35") (name "/EEM2_0_N") (class "Default")
      (node (ref "J3") (pin "3") (pinfunction "3_3") (pintype "bidirectional"))
      (node (ref "R204") (pin "2") (pinfunction "2_2") (pintype "passive"))
      (node (ref "R73") (pin "1") (pinfunction "1_1") (pintype "passive"))
    )
    (net (code "36") (name "/EEM2_0_P") (class "Default")
      (node (ref "J3") (pin "2") (pinfunction "2_2") (pintype "bidirectional"))
      (node (ref "R205") (pin "2") (pinfunction "2_2") (pintype "passive"))
      (node (ref "R73") (pin "2") (pinfunction "2_2") (pintype "passive"))
    )
    (net (code "37") (name "/EEM2_1_N") (class "Default")
      (node (ref "J3") (pin "6") (pinfunction "6_6") (pintype "bidirectional"))
      (node (ref "R218") (pin "2") (pinfunction "2_2") (pintype "passive"))
      (node (ref "R87") (pin "1") (pinfunction "1_1") (pintype "passive"))
    )
    (net (code "38") (name "/EEM2_1_P") (class "Default")
      (node (ref "J3") (pin "5") (pinfunction "5_5") (pintype "bidirectional"))
      (node (ref "R219") (pin "2") (pinfunction "2_2") (pintype "passive"))
      (node (ref "R87") (pin "2") (pinfunction "2_2") (pintype "passive"))
    )
    (net (code "39") (name "/EEM2_2_N") (class "Default")
      (node (ref "J3") (pin "9") (pinfunction "9_9") (pintype "bidirectional"))
      (node (ref "R220") (pin "2") (pinfunction "2_2") (pintype "passive"))
      (node (ref "R89") (pin "1") (pinfunction "1_1") (pintype "passive"))
    )
    (net (code "40") (name "/EEM2_2_P") (class "Default")
      (node (ref "J3") (pin "8") (pinfunction "8_8") (pintype "bidirectional"))
      (node (ref "R221") (pin "2") (pinfunction "2_2") (pintype "passive"))
      (node (ref "R89") (pin "2") (pinfunction "2_2") (pintype "passive"))
    )
    (net (code "41") (name "/EEM2_3_N") (class "Default")
      (node (ref "J3") (pin "12") (pinfunction "12_12") (pintype "bidirectional"))
      (node (ref "R136") (pin "1") (pinfunction "1_1") (pintype "passive"))
      (node (ref "R222") (pin "2") (pinfunction "2_2") (pintype "passive"))
    )
    (net (code "42") (name "/EEM2_3_P") (class "Default")
      (node (ref "J3") (pin "11") (pinfunction "11_11") (pintype "bidirectional"))
      (node (ref "R136") (pin "2") (pinfunction "2_2") (pintype "passive"))
      (node (ref "R223") (pin "2") (pinfunction "2_2") (pintype "passive"))
    )
    (net (code "43") (name "/EEM2_4_N") (class "Default")
      (node (ref "J3") (pin "15") (pinfunction "15_15") (pintype "bidirectional"))
      (node (ref "R138") (pin "1") (pinfunction "1_1") (pintype "passive"))
      (node (ref "R224") (pin "2") (pinfunction "2_2") (pintype "passive"))
    )
    (net (code "44") (name "/EEM2_4_P") (class "Default")
      (node (ref "J3") (pin "14") (pinfunction "14_14") (pintype "bidirectional"))
      (node (ref "R138") (pin "2") (pinfunction "2_2") (pintype "passive"))
      (node (ref "R225") (pin "2") (pinfunction "2_2") (pintype "passive"))
    )
    (net (code "45") (name "/EEM2_5_N") (class "Default")
      (node (ref "J3") (pin "18") (pinfunction "18_18") (pintype "bidirectional"))
      (node (ref "R140") (pin "1") (pinfunction "1_1") (pintype "passive"))
      (node (ref "R226") (pin "2") (pinfunction "2_2") (pintype "passive"))
    )
    (net (code "46") (name "/EEM2_5_P") (class "Default")
      (node (ref "J3") (pin "17") (pinfunction "17_17") (pintype "bidirectional"))
      (node (ref "R140") (pin "2") (pinfunction "2_2") (pintype "passive"))
      (node (ref "R227") (pin "2") (pinfunction "2_2") (pintype "passive"))
    )
    (net (code "47") (name "/EEM2_6_N") (class "Default")
      (node (ref "J3") (pin "21") (pinfunction "21_21") (pintype "bidirectional"))
      (node (ref "R142") (pin "1") (pinfunction "1_1") (pintype "passive"))
      (node (ref "R228") (pin "2") (pinfunction "2_2") (pintype "passive"))
    )
    (net (code "48") (name "/EEM2_6_P") (class "Default")
      (node (ref "J3") (pin "20") (pinfunction "20_20") (pintype "bidirectional"))
      (node (ref "R142") (pin "2") (pinfunction "2_2") (pintype "passive"))
      (node (ref "R229") (pin "2") (pinfunction "2_2") (pintype "passive"))
    )
    (net (code "49") (name "/EEM2_7_N") (class "Default")
      (node (ref "J3") (pin "24") (pinfunction "24_24") (pintype "bidirectional"))
      (node (ref "R144") (pin "1") (pinfunction "1_1") (pintype "passive"))
      (node (ref "R230") (pin "2") (pinfunction "2_2") (pintype "passive"))
    )
    (net (code "50") (name "/EEM2_7_P") (class "Default")
      (node (ref "J3") (pin "23") (pinfunction "23_23") (pintype "bidirectional"))
      (node (ref "R144") (pin "2") (pinfunction "2_2") (pintype "passive"))
      (node (ref "R231") (pin "2") (pinfunction "2_2") (pintype "passive"))
    )
    (net (code "51") (name "/EEMR0_0_N") (class "Default")
      (node (ref "R206") (pin "1") (pinfunction "1_1") (pintype "passive"))
      (node (ref "U1") (pin "H1") (pinfunction "IOL_14B_H1") (pintype "bidirectional"))
    )
    (net (code "52") (name "/EEMR0_0_P") (class "Default")
      (node (ref "R207") (pin "1") (pinfunction "1_1") (pintype "passive"))
      (node (ref "U1") (pin "J3") (pinfunction "IOL_14A_GBIN6_J3") (pintype "bidirectional"))
    )
    (net (code "53") (name "/EEMR0_1_N") (class "Default")
      (node (ref "R176") (pin "1") (pinfunction "1_1") (pintype "passive"))
      (node (ref "U1") (pin "B1") (pinfunction "IOL_2B_B1") (pintype "bidirectional"))
    )
    (net (code "54") (name "/EEMR0_1_P") (class "Default")
      (node (ref "R178") (pin "1") (pinfunction "1_1") (pintype "passive"))
      (node (ref "U1") (pin "F5") (pinfunction "IOL_2A_F5") (pintype "bidirectional"))
    )
    (net (code "55") (name "/EEMR0_2_N") (class "Default")
      (node (ref "R180") (pin "1") (pinfunction "1_1") (pintype "passive"))
      (node (ref "U1") (pin "C2") (pinfunction "IOL_3B_C2") (pintype "bidirectional"))
    )
    (net (code "56") (name "/EEMR0_2_P") (class "Default")
      (node (ref "R182") (pin "1") (pinfunction "1_1") (pintype "passive"))
      (node (ref "U1") (pin "C1") (pinfunction "IOL_3A_C1") (pintype "bidirectional"))
    )
    (net (code "57") (name "/EEMR0_3_N") (class "Default")
      (node (ref "R184") (pin "1") (pinfunction "1_1") (pintype "passive"))
      (node (ref "U1") (pin "D2") (pinfunction "IOL_4B_D2") (pintype "bidirectional"))
    )
    (net (code "58") (name "/EEMR0_3_P") (class "Default")
      (node (ref "R186") (pin "1") (pinfunction "1_1") (pintype "passive"))
      (node (ref "U1") (pin "F4") (pinfunction "IOL_4A_F4") (pintype "bidirectional"))
    )
    (net (code "59") (name "/EEMR0_4_N") (class "Default")
      (node (ref "R216") (pin "1") (pinfunction "1_1") (pintype "passive"))
      (node (ref "U1") (pin "L3") (pinfunction "IOL_19B_L3") (pintype "bidirectional"))
    )
    (net (code "60") (name "/EEMR0_4_P") (class "Default")
      (node (ref "R217") (pin "1") (pinfunction "1_1") (pintype "passive"))
      (node (ref "U1") (pin "L6") (pinfunction "IOL_19A_L6") (pintype "bidirectional"))
    )
    (net (code "61") (name "/EEMR0_5_N") (class "Default")
      (node (ref "R190") (pin "1") (pinfunction "1_1") (pintype "passive"))
      (node (ref "U1") (pin "E3") (pinfunction "IOL_6B_E3") (pintype "bidirectional"))
    )
    (net (code "62") (name "/EEMR0_5_P") (class "Default")
      (node (ref "R191") (pin "1") (pinfunction "1_1") (pintype "passive"))
      (node (ref "U1") (pin "G4") (pinfunction "IOL_6A_G4") (pintype "bidirectional"))
    )
    (net (code "63") (name "/EEMR0_6_N") (class "Default")
      (node (ref "R192") (pin "1") (pinfunction "1_1") (pintype "passive"))
      (node (ref "U1") (pin "E2") (pinfunction "IOL_7B_E2") (pintype "bidirectional"))
    )
    (net (code "64") (name "/EEMR0_6_P") (class "Default")
      (node (ref "R193") (pin "1") (pinfunction "1_1") (pintype "passive"))
      (node (ref "U1") (pin "H5") (pinfunction "IOL_7A_H5") (pintype "bidirectional"))
    )
    (net (code "65") (name "/EEMR0_7_N") (class "Default")
      (node (ref "R194") (pin "1") (pinfunction "1_1") (pintype "passive"))
      (node (ref "U1") (pin "F3") (pinfunction "IOL_8B_F3") (pintype "bidirectional"))
    )
    (net (code "66") (name "/EEMR0_7_P") (class "Default")
      (node (ref "R195") (pin "1") (pinfunction "1_1") (pintype "passive"))
      (node (ref "U1") (pin "G3") (pinfunction "IOL_8A_G3") (pintype "bidirectional"))
    )
    (net (code "67") (name "/EEMR1_0_N") (class "Default")
      (node (ref "R188") (pin "1") (pinfunction "1_1") (pintype "passive"))
      (node (ref "U1") (pin "D1") (pinfunction "IOL_5B_D1") (pintype "bidirectional"))
    )
    (net (code "68") (name "/EEMR1_0_P") (class "Default")
      (node (ref "R189") (pin "1") (pinfunction "1_1") (pintype "passive"))
      (node (ref "U1") (pin "G5") (pinfunction "IOL_5A_G5") (pintype "bidirectional"))
    )
    (net (code "69") (name "/EEMR1_1_N") (class "Default")
      (node (ref "R196") (pin "1") (pinfunction "1_1") (pintype "passive"))
      (node (ref "U1") (pin "F1") (pinfunction "IOL_10B_F1") (pintype "bidirectional"))
    )
    (net (code "70") (name "/EEMR1_1_P") (class "Default")
      (node (ref "R197") (pin "1") (pinfunction "1_1") (pintype "passive"))
      (node (ref "U1") (pin "H6") (pinfunction "IOL_10A_H6") (pintype "bidirectional"))
    )
    (net (code "71") (name "/EEMR1_2_N") (class "Default")
      (node (ref "R198") (pin "1") (pinfunction "1_1") (pintype "passive"))
      (node (ref "U1") (pin "G2") (pinfunction "IOL_11B_G2") (pintype "bidirectional"))
    )
    (net (code "72") (name "/EEMR1_2_P") (class "Default")
      (node (ref "R199") (pin "1") (pinfunction "1_1") (pintype "passive"))
      (node (ref "U1") (pin "H4") (pinfunction "IOL_11A_H4") (pintype "bidirectional"))
    )
    (net (code "73") (name "/EEMR1_3_N") (class "Default")
      (node (ref "R200") (pin "1") (pinfunction "1_1") (pintype "passive"))
      (node (ref "U1") (pin "H2") (pinfunction "IOL_12B_H2") (pintype "bidirectional"))
    )
    (net (code "74") (name "/EEMR1_3_P") (class "Default")
      (node (ref "R203") (pin "1") (pinfunction "1_1") (pintype "passive"))
      (node (ref "U1") (pin "J4") (pinfunction "IOL_12A_J4") (pintype "bidirectional"))
    )
    (net (code "75") (name "/EEMR1_4_N") (class "Default")
      (node (ref "R208") (pin "1") (pinfunction "1_1") (pintype "passive"))
      (node (ref "U1") (pin "J1") (pinfunction "IOL_15B_J1") (pintype "bidirectional"))
    )
    (net (code "76") (name "/EEMR1_4_P") (class "Default")
      (node (ref "R209") (pin "1") (pinfunction "1_1") (pintype "passive"))
      (node (ref "U1") (pin "J2") (pinfunction "IOL_15A_J2") (pintype "bidirectional"))
    )
    (net (code "77") (name "/EEMR1_5_N") (class "Default")
      (node (ref "R210") (pin "1") (pinfunction "1_1") (pintype "passive"))
      (node (ref "U1") (pin "K3") (pinfunction "IOL_16B_K3") (pintype "bidirectional"))
    )
    (net (code "78") (name "/EEMR1_5_P") (class "Default")
      (node (ref "R211") (pin "1") (pinfunction "1_1") (pintype "passive"))
      (node (ref "U1") (pin "K1") (pinfunction "IOL_16A_K1") (pintype "bidirectional"))
    )
    (net (code "79") (name "/EEMR1_6_N") (class "Default")
      (node (ref "R212") (pin "1") (pinfunction "1_1") (pintype "passive"))
      (node (ref "U1") (pin "L1") (pinfunction "IOL_17B_L1") (pintype "bidirectional"))
    )
    (net (code "80") (name "/EEMR1_6_P") (class "Default")
      (node (ref "R213") (pin "1") (pinfunction "1_1") (pintype "passive"))
      (node (ref "U1") (pin "L4") (pinfunction "IOL_17A_L4") (pintype "bidirectional"))
    )
    (net (code "81") (name "/EEMR1_7_N") (class "Default")
      (node (ref "R214") (pin "1") (pinfunction "1_1") (pintype "passive"))
      (node (ref "U1") (pin "M1") (pinfunction "IOL_18B_M1") (pintype "bidirectional"))
    )
    (net (code "82") (name "/EEMR1_7_P") (class "Default")
      (node (ref "R215") (pin "1") (pinfunction "1_1") (pintype "passive"))
      (node (ref "U1") (pin "K4") (pinfunction "IOL_18A_K4") (pintype "bidirectional"))
    )
    (net (code "83") (name "/EEMR2_0_N") (class "Default")
      (node (ref "R204") (pin "1") (pinfunction "1_1") (pintype "passive"))
      (node (ref "U1") (pin "G1") (pinfunction "IOL_13B_GBIN7_G1") (pintype "bidirectional"))
    )
    (net (code "84") (name "/EEMR2_0_P") (class "Default")
      (node (ref "R205") (pin "1") (pinfunction "1_1") (pintype "passive"))
      (node (ref "U1") (pin "J5") (pinfunction "IOL_13A_J5") (pintype "bidirectional"))
    )
    (net (code "85") (name "/EEMR2_1_N") (class "Default")
      (node (ref "R218") (pin "1") (pinfunction "1_1") (pintype "passive"))
      (node (ref "U1") (pin "M2") (pinfunction "IOL_20B_M2") (pintype "bidirectional"))
    )
    (net (code "86") (name "/EEMR2_1_P") (class "Default")
      (node (ref "R219") (pin "1") (pinfunction "1_1") (pintype "passive"))
      (node (ref "U1") (pin "K5") (pinfunction "IOL_20A_K5") (pintype "bidirectional"))
    )
    (net (code "87") (name "/EEMR2_2_N") (class "Default")
      (node (ref "R220") (pin "1") (pinfunction "1_1") (pintype "passive"))
      (node (ref "U1") (pin "N2") (pinfunction "IOL_21B_N2") (pintype "bidirectional"))
    )
    (net (code "88") (name "/EEMR2_2_P") (class "Default")
      (node (ref "R221") (pin "1") (pinfunction "1_1") (pintype "passive"))
      (node (ref "U1") (pin "L7") (pinfunction "IOL_21A_L7") (pintype "bidirectional"))
    )
    (net (code "89") (name "/EEMR2_3_N") (class "Default")
      (node (ref "R222") (pin "1") (pinfunction "1_1") (pintype "passive"))
      (node (ref "U1") (pin "M3") (pinfunction "IOL_22B_M3") (pintype "bidirectional"))
    )
    (net (code "90") (name "/EEMR2_3_P") (class "Default")
      (node (ref "R223") (pin "1") (pinfunction "1_1") (pintype "passive"))
      (node (ref "U1") (pin "M6") (pinfunction "IOL_22A_M6") (pintype "bidirectional"))
    )
    (net (code "91") (name "/EEMR2_4_N") (class "Default")
      (node (ref "R224") (pin "1") (pinfunction "1_1") (pintype "passive"))
      (node (ref "U1") (pin "N3") (pinfunction "IOL_23B_N3") (pintype "bidirectional"))
    )
    (net (code "92") (name "/EEMR2_4_P") (class "Default")
      (node (ref "R225") (pin "1") (pinfunction "1_1") (pintype "passive"))
      (node (ref "U1") (pin "L5") (pinfunction "IOL_23A_L5") (pintype "bidirectional"))
    )
    (net (code "93") (name "/EEMR2_5_N") (class "Default")
      (node (ref "R226") (pin "1") (pinfunction "1_1") (pintype "passive"))
      (node (ref "U1") (pin "M4") (pinfunction "IOL_24B_M4") (pintype "bidirectional"))
    )
    (net (code "94") (name "/EEMR2_5_P") (class "Default")
      (node (ref "R227") (pin "1") (pinfunction "1_1") (pintype "passive"))
      (node (ref "U1") (pin "P1") (pinfunction "IOL_24A_P1") (pintype "bidirectional"))
    )
    (net (code "95") (name "/EEMR2_6_N") (class "Default")
      (node (ref "R228") (pin "1") (pinfunction "1_1") (pintype "passive"))
      (node (ref "U1") (pin "M5") (pinfunction "IOL_25B_M5") (pintype "bidirectional"))
    )
    (net (code "96") (name "/EEMR2_6_P") (class "Default")
      (node (ref "R229") (pin "1") (pinfunction "1_1") (pintype "passive"))
      (node (ref "U1") (pin "P2") (pinfunction "IOL_25A_P2") (pintype "bidirectional"))
    )
    (net (code "97") (name "/EEMR2_7_N") (class "Default")
      (node (ref "R230") (pin "1") (pinfunction "1_1") (pintype "passive"))
      (node (ref "U1") (pin "N4") (pinfunction "IOL_26B_N4") (pintype "bidirectional"))
    )
    (net (code "98") (name "/EEMR2_7_P") (class "Default")
      (node (ref "R231") (pin "1") (pinfunction "1_1") (pintype "passive"))
      (node (ref "U1") (pin "R1") (pinfunction "IOL_26A_R1") (pintype "bidirectional"))
    )
    (net (code "99") (name "/I2C0_SCL") (class "Default")
      (node (ref "J1") (pin "27") (pinfunction "27_27") (pintype "bidirectional"))
    )
    (net (code "100") (name "/I2C0_SDA") (class "Default")
      (node (ref "J1") (pin "26") (pinfunction "26_26") (pintype "bidirectional"))
    )
    (net (code "101") (name "/I2C1_SCL") (class "Default")
      (node (ref "J2") (pin "27") (pinfunction "27_27") (pintype "bidirectional"))
    )
    (net (code "102") (name "/I2C1_SDA") (class "Default")
      (node (ref "J2") (pin "26") (pinfunction "26_26") (pintype "bidirectional"))
    )
    (net (code "103") (name "/I2C2_SCL") (class "Default")
      (node (ref "J3") (pin "27") (pinfunction "27_27") (pintype "bidirectional"))
    )
    (net (code "104") (name "/I2C2_SDA") (class "Default")
      (node (ref "J3") (pin "26") (pinfunction "26_26") (pintype "bidirectional"))
    )
    (net (code "105") (name "/I2C_RESET") (class "Default")
      (node (ref "U1") (pin "B2") (pinfunction "IOL_1B_B2") (pintype "bidirectional"))
    )
    (net (code "106") (name "/USR_LED") (class "Default")
      (node (ref "U1") (pin "H3") (pinfunction "IOL_9A_H3") (pintype "bidirectional"))
    )
    (net (code "108") (name "GND") (class "Default")
      (node (ref "J1") (pin "1") (pinfunction "1_1") (pintype "bidirectional"))
      (node (ref "J1") (pin "10") (pinfunction "10_10") (pintype "bidirectional"))
      (node (ref "J1") (pin "13") (pinfunction "13_13") (pintype "bidirectional"))
      (node (ref "J1") (pin "16") (pinfunction "16_16") (pintype "bidirectional"))
      (node (ref "J1") (pin "19") (pinfunction "19_19") (pintype "bidirectional"))
      (node (ref "J1") (pin "22") (pinfunction "22_22") (pintype "bidirectional"))
      (node (ref "J1") (pin "25") (pinfunction "25_25") (pintype "bidirectional"))
      (node (ref "J1") (pin "4") (pinfunction "4_4") (pintype "bidirectional"))
      (node (ref "J1") (pin "7") (pinfunction "7_7") (pintype "bidirectional"))
      (node (ref "J2") (pin "1") (pinfunction "1_1") (pintype "bidirectional"))
      (node (ref "J2") (pin "10") (pinfunction "10_10") (pintype "bidirectional"))
      (node (ref "J2") (pin "13") (pinfunction "13_13") (pintype "bidirectional"))
      (node (ref "J2") (pin "16") (pinfunction "16_16") (pintype "bidirectional"))
      (node (ref "J2") (pin "19") (pinfunction "19_19") (pintype "bidirectional"))
      (node (ref "J2") (pin "22") (pinfunction "22_22") (pintype "bidirectional"))
      (node (ref "J2") (pin "25") (pinfunction "25_25") (pintype "bidirectional"))
      (node (ref "J2") (pin "4") (pinfunction "4_4") (pintype "bidirectional"))
      (node (ref "J2") (pin "7") (pinfunction "7_7") (pintype "bidirectional"))
      (node (ref "J3") (pin "1") (pinfunction "1_1") (pintype "bidirectional"))
      (node (ref "J3") (pin "10") (pinfunction "10_10") (pintype "bidirectional"))
      (node (ref "J3") (pin "13") (pinfunction "13_13") (pintype "bidirectional"))
      (node (ref "J3") (pin "16") (pinfunction "16_16") (pintype "bidirectional"))
      (node (ref "J3") (pin "19") (pinfunction "19_19") (pintype "bidirectional"))
      (node (ref "J3") (pin "22") (pinfunction "22_22") (pintype "bidirectional"))
      (node (ref "J3") (pin "25") (pinfunction "25_25") (pintype "bidirectional"))
      (node (ref "J3") (pin "4") (pinfunction "4_4") (pintype "bidirectional"))
      (node (ref "J3") (pin "7") (pinfunction "7_7") (pintype "bidirectional"))
    )
    (net (code "109") (name "Net-(U1D-IOL_1A)") (class "Default")
      (node (ref "B14") (pin "1") (pinfunction "1_1") (pintype "bidirectional"))
      (node (ref "U1") (pin "E4") (pinfunction "IOL_1A_E4") (pintype "bidirectional"))
    )
    (net (code "110") (name "P2V5") (class "Default")
      (node (ref "R65") (pin "2") (pinfunction "2_2") (pintype "passive"))
    )
    (net (code "111") (name "P3V3MP") (class "Default")
      (node (ref "J1") (pin "30") (pinfunction "30_30") (pintype "bidirectional"))
      (node (ref "J2") (pin "30") (pinfunction "30_30") (pintype "bidirectional"))
      (node (ref "J3") (pin "30") (pinfunction "30_30") (pintype "bidirectional"))
    )
    (net (code "112") (name "P12V0") (class "Default")
      (node (ref "J1") (pin "28") (pinfunction "28_28") (pintype "bidirectional"))
      (node (ref "J1") (pin "29") (pinfunction "29_29") (pintype "bidirectional"))
      (node (ref "J2") (pin "28") (pinfunction "28_28") (pintype "bidirectional"))
      (node (ref "J2") (pin "29") (pinfunction "29_29") (pintype "bidirectional"))
      (node (ref "J3") (pin "28") (pinfunction "28_28") (pintype "bidirectional"))
      (node (ref "J3") (pin "29") (pinfunction "29_29") (pintype "bidirectional"))
    )
  )
)
